# highpowerboard.net
KiCad netlist of a schematic drawn in EAGLE
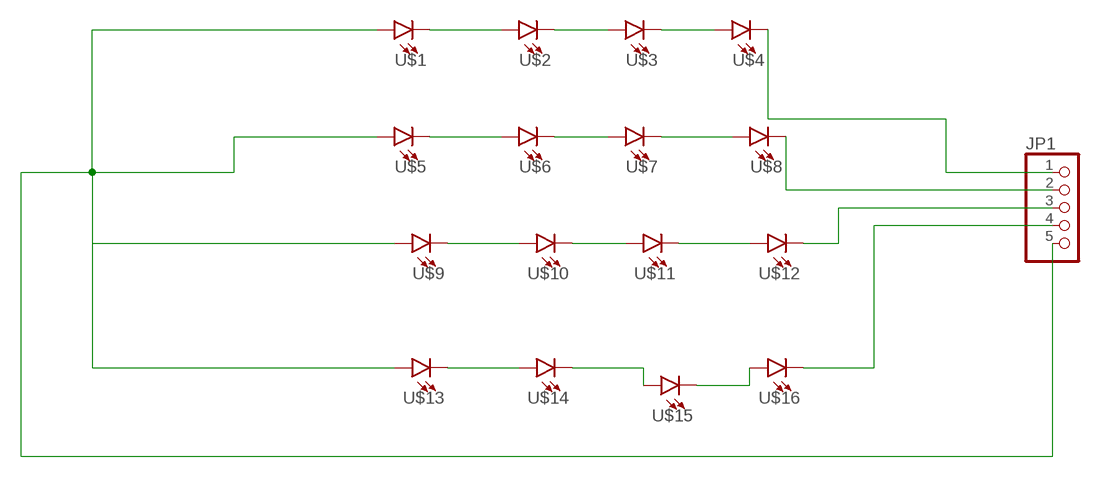
[diagram p0: schematic, sheet 1]

(export (version "E")
  (design (tool "Eeschema 10.0.6"))
  (components
    (comp (ref "JP1")
      (value "PINHD-1X05_2.54-SMD-90°")
      (footprint "eagle-import:1X05SMD_90")
      (libsource (lib "eagle-import") (part "PINHD-1X05_2.54-SMD-90°"))
    )
    (comp (ref "U$1")
      (value "LEDHIGHPOWER")
      (footprint "eagle-import:HIGHPOWERLED")
      (libsource (lib "eagle-import") (part "LEDHIGHPOWER"))
    )
    (comp (ref "U$2")
      (value "LEDHIGHPOWER")
      (footprint "eagle-import:HIGHPOWERLED")
      (libsource (lib "eagle-import") (part "LEDHIGHPOWER"))
    )
    (comp (ref "U$3")
      (value "LEDHIGHPOWER")
      (footprint "eagle-import:HIGHPOWERLED")
      (libsource (lib "eagle-import") (part "LEDHIGHPOWER"))
    )
    (comp (ref "U$4")
      (value "LEDHIGHPOWER")
      (footprint "eagle-import:HIGHPOWERLED")
      (libsource (lib "eagle-import") (part "LEDHIGHPOWER"))
    )
    (comp (ref "U$5")
      (value "LEDHIGHPOWER")
      (footprint "eagle-import:HIGHPOWERLED")
      (libsource (lib "eagle-import") (part "LEDHIGHPOWER"))
    )
    (comp (ref "U$6")
      (value "LEDHIGHPOWER")
      (footprint "eagle-import:HIGHPOWERLED")
      (libsource (lib "eagle-import") (part "LEDHIGHPOWER"))
    )
    (comp (ref "U$7")
      (value "LEDHIGHPOWER")
      (footprint "eagle-import:HIGHPOWERLED")
      (libsource (lib "eagle-import") (part "LEDHIGHPOWER"))
    )
    (comp (ref "U$8")
      (value "LEDHIGHPOWER")
      (footprint "eagle-import:HIGHPOWERLED")
      (libsource (lib "eagle-import") (part "LEDHIGHPOWER"))
    )
    (comp (ref "U$9")
      (value "LEDHIGHPOWER")
      (footprint "eagle-import:HIGHPOWERLED")
      (libsource (lib "eagle-import") (part "LEDHIGHPOWER"))
    )
    (comp (ref "U$10")
      (value "LEDHIGHPOWER")
      (footprint "eagle-import:HIGHPOWERLED")
      (libsource (lib "eagle-import") (part "LEDHIGHPOWER"))
    )
    (comp (ref "U$11")
      (value "LEDHIGHPOWER")
      (footprint "eagle-import:HIGHPOWERLED")
      (libsource (lib "eagle-import") (part "LEDHIGHPOWER"))
    )
    (comp (ref "U$12")
      (value "LEDHIGHPOWER")
      (footprint "eagle-import:HIGHPOWERLED")
      (libsource (lib "eagle-import") (part "LEDHIGHPOWER"))
    )
    (comp (ref "U$13")
      (value "LEDHIGHPOWER")
      (footprint "eagle-import:HIGHPOWERLED")
      (libsource (lib "eagle-import") (part "LEDHIGHPOWER"))
    )
    (comp (ref "U$14")
      (value "LEDHIGHPOWER")
      (footprint "eagle-import:HIGHPOWERLED")
      (libsource (lib "eagle-import") (part "LEDHIGHPOWER"))
    )
    (comp (ref "U$15")
      (value "LEDHIGHPOWER")
      (footprint "eagle-import:HIGHPOWERLED")
      (libsource (lib "eagle-import") (part "LEDHIGHPOWER"))
    )
    (comp (ref "U$16")
      (value "LEDHIGHPOWER")
      (footprint "eagle-import:HIGHPOWERLED")
      (libsource (lib "eagle-import") (part "LEDHIGHPOWER"))
    )
  )
  (nets
    (net (code "1") (name "Net-(U$1-A)") (class "Default")
      (node (ref "JP1") (pin "5") (pinfunction "5_5") (pintype "passive"))
      (node (ref "U$1") (pin "PO$") (pinfunction "A_PO$") (pintype "passive"))
      (node (ref "U$13") (pin "PO$") (pinfunction "A_PO$") (pintype "passive"))
      (node (ref "U$5") (pin "PO$") (pinfunction "A_PO$") (pintype "passive"))
      (node (ref "U$9") (pin "PO$") (pinfunction "A_PO$") (pintype "passive"))
    )
    (net (code "2") (name "Net-(U$1-C)") (class "Default")
      (node (ref "U$1") (pin "PI$") (pinfunction "C_PI$") (pintype "passive"))
      (node (ref "U$2") (pin "PO$") (pinfunction "A_PO$") (pintype "passive"))
    )
    (net (code "3") (name "Net-(U$2-C)") (class "Default")
      (node (ref "U$2") (pin "PI$") (pinfunction "C_PI$") (pintype "passive"))
      (node (ref "U$3") (pin "PO$") (pinfunction "A_PO$") (pintype "passive"))
    )
    (net (code "4") (name "Net-(U$3-C)") (class "Default")
      (node (ref "U$3") (pin "PI$") (pinfunction "C_PI$") (pintype "passive"))
      (node (ref "U$4") (pin "PO$") (pinfunction "A_PO$") (pintype "passive"))
    )
    (net (code "5") (name "Net-(U$4-C)") (class "Default")
      (node (ref "JP1") (pin "1") (pinfunction "1_1") (pintype "passive"))
      (node (ref "U$4") (pin "PI$") (pinfunction "C_PI$") (pintype "passive"))
    )
    (net (code "6") (name "Net-(U$5-C)") (class "Default")
      (node (ref "U$5") (pin "PI$") (pinfunction "C_PI$") (pintype "passive"))
      (node (ref "U$6") (pin "PO$") (pinfunction "A_PO$") (pintype "passive"))
    )
    (net (code "7") (name "Net-(U$6-C)") (class "Default")
      (node (ref "U$6") (pin "PI$") (pinfunction "C_PI$") (pintype "passive"))
      (node (ref "U$7") (pin "PO$") (pinfunction "A_PO$") (pintype "passive"))
    )
    (net (code "8") (name "Net-(U$7-C)") (class "Default")
      (node (ref "U$7") (pin "PI$") (pinfunction "C_PI$") (pintype "passive"))
      (node (ref "U$8") (pin "PO$") (pinfunction "A_PO$") (pintype "passive"))
    )
    (net (code "9") (name "Net-(U$8-C)") (class "Default")
      (node (ref "JP1") (pin "2") (pinfunction "2_2") (pintype "passive"))
      (node (ref "U$8") (pin "PI$") (pinfunction "C_PI$") (pintype "passive"))
    )
    (net (code "10") (name "Net-(U$10-A)") (class "Default")
      (node (ref "U$10") (pin "PO$") (pinfunction "A_PO$") (pintype "passive"))
      (node (ref "U$9") (pin "PI$") (pinfunction "C_PI$") (pintype "passive"))
    )
    (net (code "11") (name "Net-(U$10-C)") (class "Default")
      (node (ref "U$10") (pin "PI$") (pinfunction "C_PI$") (pintype "passive"))
      (node (ref "U$11") (pin "PO$") (pinfunction "A_PO$") (pintype "passive"))
    )
    (net (code "12") (name "Net-(U$11-C)") (class "Default")
      (node (ref "U$11") (pin "PI$") (pinfunction "C_PI$") (pintype "passive"))
      (node (ref "U$12") (pin "PO$") (pinfunction "A_PO$") (pintype "passive"))
    )
    (net (code "13") (name "Net-(U$12-C)") (class "Default")
      (node (ref "JP1") (pin "3") (pinfunction "3_3") (pintype "passive"))
      (node (ref "U$12") (pin "PI$") (pinfunction "C_PI$") (pintype "passive"))
    )
    (net (code "14") (name "Net-(U$13-C)") (class "Default")
      (node (ref "U$13") (pin "PI$") (pinfunction "C_PI$") (pintype "passive"))
      (node (ref "U$14") (pin "PO$") (pinfunction "A_PO$") (pintype "passive"))
    )
    (net (code "15") (name "Net-(U$14-C)") (class "Default")
      (node (ref "U$14") (pin "PI$") (pinfunction "C_PI$") (pintype "passive"))
      (node (ref "U$15") (pin "PO$") (pinfunction "A_PO$") (pintype "passive"))
    )
    (net (code "16") (name "Net-(U$15-C)") (class "Default")
      (node (ref "U$15") (pin "PI$") (pinfunction "C_PI$") (pintype "passive"))
      (node (ref "U$16") (pin "PO$") (pinfunction "A_PO$") (pintype "passive"))
    )
    (net (code "17") (name "Net-(U$16-C)") (class "Default")
      (node (ref "JP1") (pin "4") (pinfunction "4_4") (pintype "passive"))
      (node (ref "U$16") (pin "PI$") (pinfunction "C_PI$") (pintype "passive"))
    )
  )
)
